# Bluetooth_Bridge_v16_Schematic_EasyEDA.net
KiCad netlist of a schematic drawn in EasyEDA
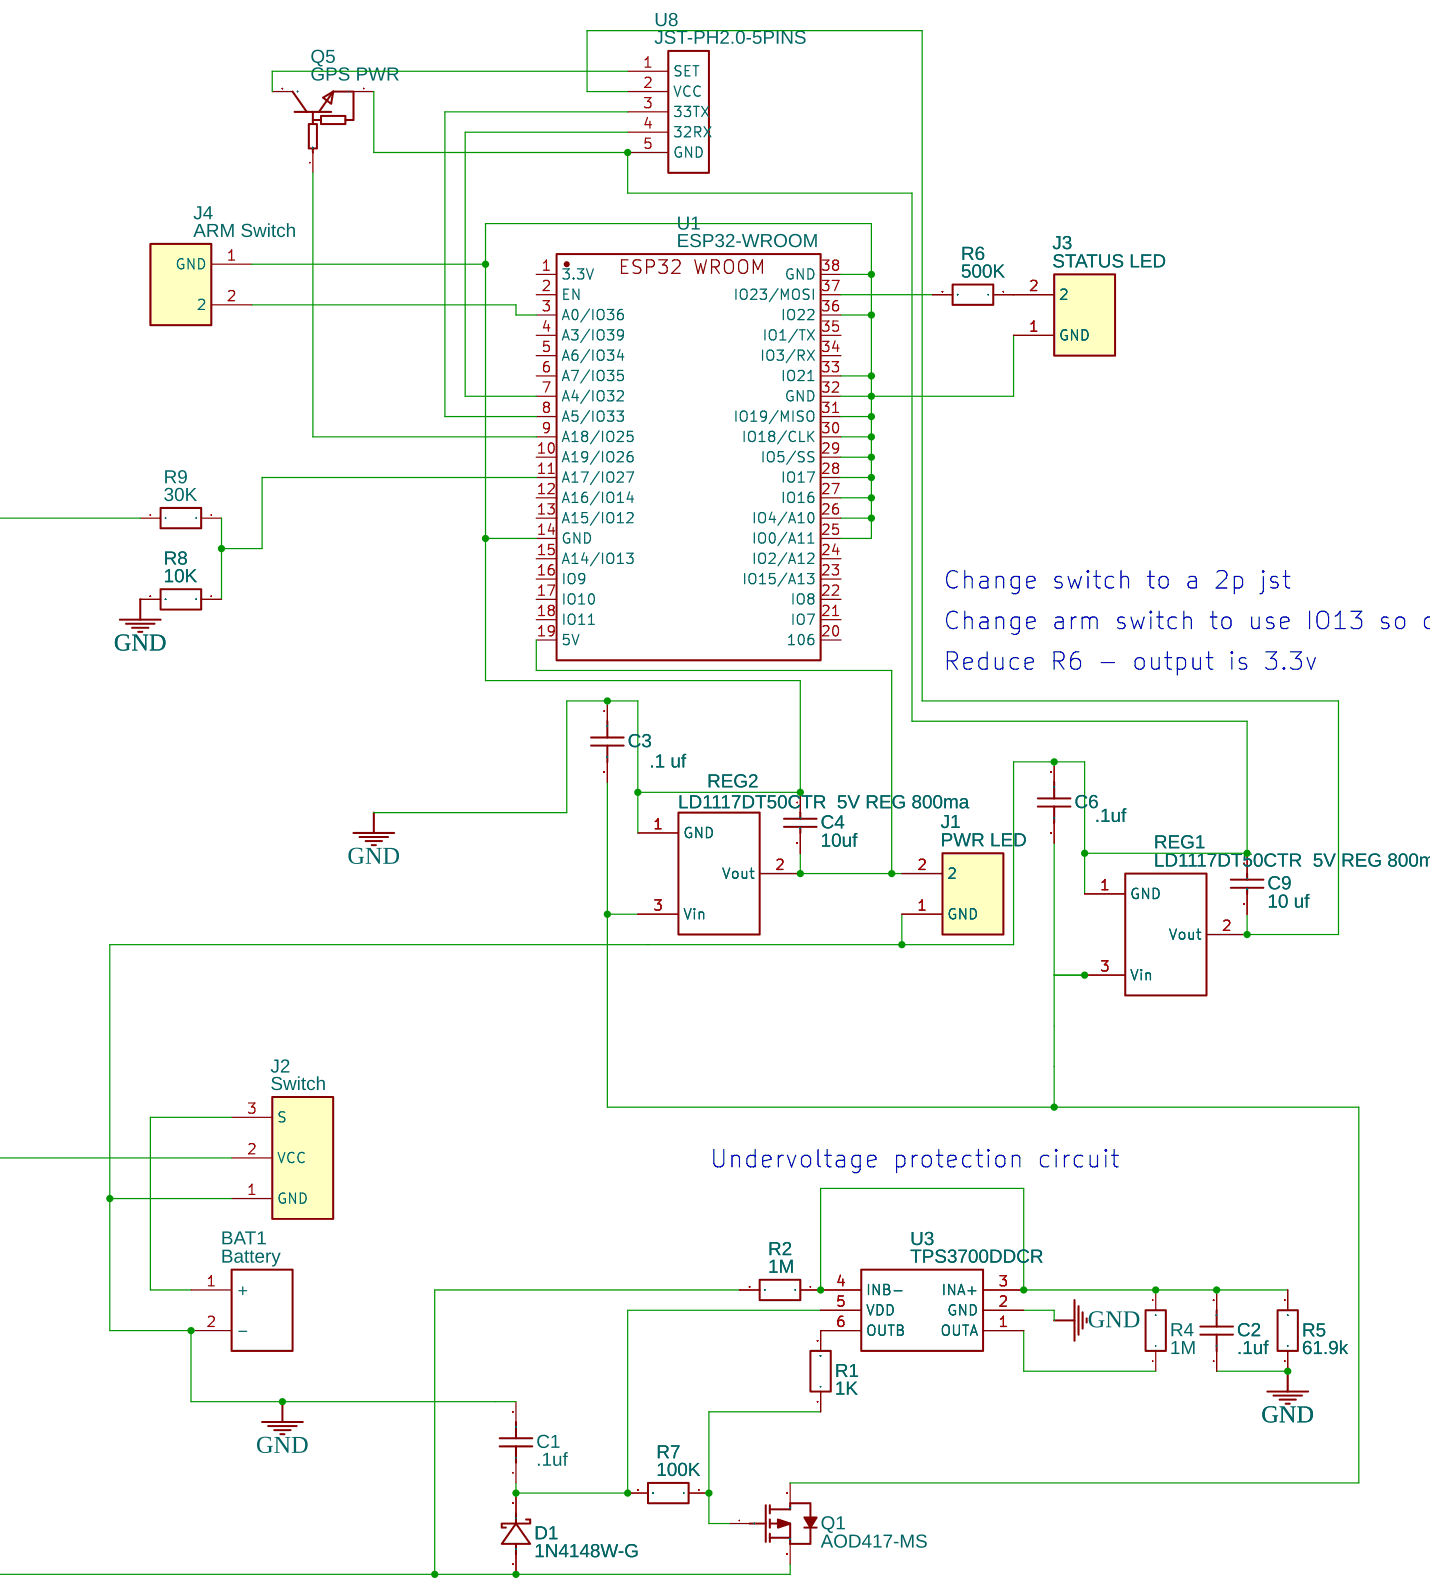
[diagram p0: schematic sheet]

(export (version "E")
  (design (tool "Eeschema 10.0.6"))
  (components
    (comp (ref "BAT1")
      (value "Battery")
      (fields
        (field (name "Manufacturer Part") "MKDSN1.5/2-5.08")
        (field (name "Manufacturer") "Phoenix Contact")
      )
      (libsource (lib "") (part "Unknown_85_-285"))
    )
    (comp (ref "C1")
      (value ".1uf")
      (fields
        (field (name "Manufacturer Part") "CS2012X7R105K500NRE")
        (field (name "Manufacturer") "Samwha Capacitor")
      )
      (libsource (lib "") (part "CS2012X7R105K500NRE"))
    )
    (comp (ref "C2")
      (value ".1uf")
      (fields
        (field (name "Manufacturer Part") "CS2012X7R105K500NRE")
        (field (name "Manufacturer") "Samwha Capacitor")
      )
      (libsource (lib "") (part "CS2012X7R105K500NRE"))
    )
    (comp (ref "C3")
      (value ".1 uf")
      (fields (field (name "Manufacturer Part") "CC0402KRX7R6BB104") (field (name "Manufacturer") "YAGEO"))
      (libsource (lib "") (part "CC0402KRX7R6BB104"))
    )
    (comp (ref "C4")
      (value "10uf")
      (fields (field (name "Manufacturer Part") "CL05A106MQ5NUNC") (field (name "Manufacturer") "SAMSUNG"))
      (libsource (lib "") (part "CL05A106MQ5NUNC"))
    )
    (comp (ref "C6")
      (value ".1uf")
      (fields (field (name "Manufacturer Part") "CC0402KRX7R6BB104") (field (name "Manufacturer") "YAGEO"))
      (libsource (lib "") (part "CC0402KRX7R6BB104"))
    )
    (comp (ref "C9")
      (value "10 uf")
      (fields (field (name "Manufacturer Part") "CL05A106MQ5NUNC") (field (name "Manufacturer") "SAMSUNG"))
      (libsource (lib "") (part "CL05A106MQ5NUNC"))
    )
    (comp (ref "D1")
      (value "1N4148W-G")
      (fields (field (name "Manufacturer Part") "DS16W(S16)-SOD123"))
      (libsource (lib "") (part "DS16W(S16)-SOD123"))
    )
    (comp (ref "J1")
      (value "PWR LED")
      (fields (field (name "Manufacturer Part") "B2B-PH-K-S(LF)(SN)") (field (name "Manufacturer") "JST"))
      (libsource (lib "") (part "B2B-PH-K-S(LF)(SN)"))
    )
    (comp (ref "J2")
      (value "Switch")
      (fields (field (name "Manufacturer Part") "B3B-PH-K-S(LF)(SN)") (field (name "Manufacturer") "JST"))
      (libsource (lib "") (part "Unknown_105_-360"))
    )
    (comp (ref "J3")
      (value "STATUS LED")
      (fields (field (name "Manufacturer Part") "B2B-PH-K-S(LF)(SN)") (field (name "Manufacturer") "JST"))
      (libsource (lib "") (part "B2B-PH-K-S(LF)(SN)"))
    )
    (comp (ref "J4")
      (value "ARM Switch")
      (fields (field (name "Manufacturer Part") "B2B-PH-K-S(LF)(SN)") (field (name "Manufacturer") "JST"))
      (libsource (lib "") (part "B2B-PH-K-S(LF)(SN)_1"))
    )
    (comp (ref "Q1")
      (value "AOD417-MS")
      (fields (field (name "Manufacturer") "MSKSEMI(美森科)"))
      (libsource (lib "") (part "AOD417-MS"))
    )
    (comp (ref "Q5")
      (value "GPS PWR")
      (fields (field (name "Manufacturer Part") "PDTC114EU,135") (field (name "Manufacturer") "Nexperia"))
      (libsource (lib "") (part "PDTC114EU,135"))
    )
    (comp (ref "R1")
      (value "1K")
      (fields (field (name "Manufacturer Part") "ERJP06J221V") (field (name "Manufacturer") "PANASONIC"))
      (libsource (lib "") (part "ERJP06J221V"))
    )
    (comp (ref "R2")
      (value "1M")
      (fields (field (name "Manufacturer Part") "ERJP06J221V") (field (name "Manufacturer") "PANASONIC"))
      (libsource (lib "") (part "ERJP06J221V_1"))
    )
    (comp (ref "R4")
      (value "1M")
      (fields (field (name "Manufacturer Part") "ERJP06J221V") (field (name "Manufacturer") "PANASONIC"))
      (libsource (lib "") (part "ERJP06J221V"))
    )
    (comp (ref "R5")
      (value "61.9k")
      (fields (field (name "Manufacturer Part") "ERJP06J221V") (field (name "Manufacturer") "PANASONIC"))
      (libsource (lib "") (part "ERJP06J221V"))
    )
    (comp (ref "R6")
      (value "500K")
      (fields (field (name "Manufacturer Part") "ERJP06J221V") (field (name "Manufacturer") "PANASONIC"))
      (libsource (lib "") (part "ERJP06J221V_1"))
    )
    (comp (ref "R7")
      (value "100K")
      (fields (field (name "Manufacturer Part") "ERJP06J221V") (field (name "Manufacturer") "PANASONIC"))
      (libsource (lib "") (part "ERJP06J221V_1"))
    )
    (comp (ref "R8")
      (value "10K")
      (fields (field (name "Manufacturer Part") "SFR03EZPF1001") (field (name "Manufacturer") "ROHM(罗姆)"))
      (libsource (lib "") (part "SFR03EZPF1001"))
    )
    (comp (ref "R9")
      (value "30K")
      (fields (field (name "Manufacturer Part") "SFR03EZPF1001") (field (name "Manufacturer") "ROHM(罗姆)"))
      (libsource (lib "") (part "SFR03EZPF1001"))
    )
    (comp (ref "REG1")
      (value "LD1117DT50CTR  5V REG 800ma")
      (fields (field (name "Manufacturer Part") "LD1117AG-12-TN3-A-R") (field (name "Manufacturer") "UTC"))
      (libsource (lib "") (part "LD1117AG-12-TN3-A-R"))
    )
    (comp (ref "REG2")
      (value "LD1117DT50CTR  5V REG 800ma")
      (fields (field (name "Manufacturer Part") "LD1117AG-12-TN3-A-R") (field (name "Manufacturer") "UTC"))
      (libsource (lib "") (part "LD1117AG-12-TN3-A-R"))
    )
    (comp (ref "U1")
      (value "ESP32-WROOM")
      (fields (field (name "Manufacturer Part") "3-01-1287") (field (name "Manufacturer") "HiLetgo"))
      (libsource (lib "") (part "Unknown_305_-705"))
    )
    (comp (ref "U3")
      (value "TPS3700DDCR")
      (fields (field (name "Manufacturer") "TI"))
      (libsource (lib "") (part "TPS3700DDCR"))
    )
    (comp (ref "U8") (value "JST-PH2.0-5PINS") (libsource (lib "") (part "JST-PH2.0-5PINS")))
  )
  (nets
    (net (code "1") (name "GND") (class "Default")
      (node (ref "BAT1") (pin "2") (pinfunction "-_2") (pintype "unspecified"))
      (node (ref "C1") (pin "2") (pinfunction "2_2") (pintype "unspecified"))
      (node (ref "C2") (pin "1") (pinfunction "1_1") (pintype "unspecified"))
      (node (ref "C3") (pin "1") (pinfunction "1_1") (pintype "unspecified"))
      (node (ref "C4") (pin "1") (pinfunction "1_1") (pintype "input"))
      (node (ref "C6") (pin "1") (pinfunction "1_1") (pintype "unspecified"))
      (node (ref "C9") (pin "1") (pinfunction "1_1") (pintype "input"))
      (node (ref "J1") (pin "1") (pinfunction "GND_1") (pintype "input"))
      (node (ref "J2") (pin "1") (pinfunction "GND_1") (pintype "input"))
      (node (ref "J3") (pin "1") (pinfunction "GND_1") (pintype "input"))
      (node (ref "J4") (pin "1") (pinfunction "GND_1") (pintype "input"))
      (node (ref "Q5") (pin "2") (pinfunction "E_2") (pintype "unspecified"))
      (node (ref "R5") (pin "1") (pinfunction "1_1") (pintype "unspecified"))
      (node (ref "R8") (pin "2") (pinfunction "2_2") (pintype "unspecified"))
      (node (ref "REG1") (pin "1") (pinfunction "GND_1") (pintype "unspecified"))
      (node (ref "REG2") (pin "1") (pinfunction "GND_1") (pintype "unspecified"))
      (node (ref "U1") (pin "14") (pinfunction "GND_14") (pintype "unspecified"))
      (node (ref "U1") (pin "25") (pinfunction "IO0/A11_25") (pintype "unspecified"))
      (node (ref "U1") (pin "26") (pinfunction "IO4/A10_26") (pintype "unspecified"))
      (node (ref "U1") (pin "27") (pinfunction "IO16_27") (pintype "unspecified"))
      (node (ref "U1") (pin "28") (pinfunction "IO17_28") (pintype "unspecified"))
      (node (ref "U1") (pin "29") (pinfunction "IO5/SS_29") (pintype "unspecified"))
      (node (ref "U1") (pin "30") (pinfunction "IO18/CLK_30") (pintype "unspecified"))
      (node (ref "U1") (pin "31") (pinfunction "IO19/MISO_31") (pintype "unspecified"))
      (node (ref "U1") (pin "32") (pinfunction "GND_32") (pintype "unspecified"))
      (node (ref "U1") (pin "33") (pinfunction "IO21_33") (pintype "unspecified"))
      (node (ref "U1") (pin "36") (pinfunction "IO22_36") (pintype "unspecified"))
      (node (ref "U1") (pin "38") (pinfunction "GND_38") (pintype "unspecified"))
      (node (ref "U3") (pin "2") (pinfunction "GND_2") (pintype "unspecified"))
      (node (ref "U8") (pin "5") (pinfunction "GND_5") (pintype "unspecified"))
    )
    (net (code "2") (name "Net-(BAT1-+)") (class "Default")
      (node (ref "BAT1") (pin "1") (pinfunction "+_1") (pintype "unspecified"))
      (node (ref "J2") (pin "3") (pinfunction "S_3") (pintype "input"))
    )
    (net (code "3") (name "Net-(D1-A)") (class "Default")
      (node (ref "D1") (pin "1") (pinfunction "A_1") (pintype "unspecified"))
      (node (ref "J2") (pin "2") (pinfunction "VCC_2") (pintype "input"))
      (node (ref "Q1") (pin "3") (pinfunction "S_3") (pintype "unspecified"))
      (node (ref "R2") (pin "2") (pinfunction "2_2") (pintype "unspecified"))
      (node (ref "R9") (pin "2") (pinfunction "2_2") (pintype "unspecified"))
    )
    (net (code "4") (name "Net-(D1-K)") (class "Default")
      (node (ref "C1") (pin "1") (pinfunction "1_1") (pintype "unspecified"))
      (node (ref "D1") (pin "2") (pinfunction "K_2") (pintype "unspecified"))
      (node (ref "R7") (pin "2") (pinfunction "2_2") (pintype "unspecified"))
      (node (ref "U3") (pin "5") (pinfunction "VDD_5") (pintype "unspecified"))
    )
    (net (code "5") (name "Net-(J3-Pad2)") (class "Default")
      (node (ref "J3") (pin "2") (pinfunction "2_2") (pintype "input"))
      (node (ref "R6") (pin "1") (pinfunction "1_1") (pintype "unspecified"))
    )
    (net (code "6") (name "Net-(Q1-D)") (class "Default")
      (node (ref "C3") (pin "2") (pinfunction "2_2") (pintype "unspecified"))
      (node (ref "C6") (pin "2") (pinfunction "2_2") (pintype "unspecified"))
      (node (ref "Q1") (pin "2") (pinfunction "D_2") (pintype "unspecified"))
      (node (ref "REG1") (pin "3") (pinfunction "Vin_3") (pintype "unspecified"))
      (node (ref "REG2") (pin "3") (pinfunction "Vin_3") (pintype "unspecified"))
    )
    (net (code "7") (name "Net-(Q1-G)") (class "Default")
      (node (ref "Q1") (pin "1") (pinfunction "G_1") (pintype "unspecified"))
      (node (ref "R1") (pin "1") (pinfunction "1_1") (pintype "unspecified"))
      (node (ref "R7") (pin "1") (pinfunction "1_1") (pintype "unspecified"))
    )
    (net (code "8") (name "Net-(Q5-B)") (class "Default")
      (node (ref "Q5") (pin "1") (pinfunction "B_1") (pintype "unspecified"))
      (node (ref "U1") (pin "9") (pinfunction "A18/IO25_9") (pintype "unspecified"))
    )
    (net (code "9") (name "Net-(Q5-C)") (class "Default")
      (node (ref "Q5") (pin "3") (pinfunction "C_3") (pintype "unspecified"))
      (node (ref "U8") (pin "1") (pinfunction "SET_1") (pintype "unspecified"))
    )
    (net (code "10") (name "Net-(REG1-Vout)") (class "Default")
      (node (ref "C9") (pin "2") (pinfunction "2_2") (pintype "input"))
      (node (ref "REG1") (pin "2") (pinfunction "Vout_2") (pintype "unspecified"))
      (node (ref "U8") (pin "2") (pinfunction "VCC_2") (pintype "unspecified"))
    )
    (net (code "11") (name "Net-(REG2-Vout)") (class "Default")
      (node (ref "C4") (pin "2") (pinfunction "2_2") (pintype "input"))
      (node (ref "J1") (pin "2") (pinfunction "2_2") (pintype "input"))
      (node (ref "REG2") (pin "2") (pinfunction "Vout_2") (pintype "unspecified"))
      (node (ref "U1") (pin "19") (pinfunction "5V_19") (pintype "unspecified"))
    )
    (net (code "12") (name "Net-(U1-A0{slash}IO36)") (class "Default")
      (node (ref "J4") (pin "2") (pinfunction "2_2") (pintype "input"))
      (node (ref "U1") (pin "3") (pinfunction "A0/IO36_3") (pintype "unspecified"))
    )
    (net (code "13") (name "Net-(U1-A4{slash}IO32)") (class "Default")
      (node (ref "U1") (pin "7") (pinfunction "A4/IO32_7") (pintype "unspecified"))
      (node (ref "U8") (pin "4") (pinfunction "32RX_4") (pintype "unspecified"))
    )
    (net (code "14") (name "Net-(U1-A5{slash}IO33)") (class "Default")
      (node (ref "U1") (pin "8") (pinfunction "A5/IO33_8") (pintype "unspecified"))
      (node (ref "U8") (pin "3") (pinfunction "33TX_3") (pintype "unspecified"))
    )
    (net (code "15") (name "Net-(U1-A17{slash}IO27)") (class "Default")
      (node (ref "R8") (pin "1") (pinfunction "1_1") (pintype "unspecified"))
      (node (ref "R9") (pin "1") (pinfunction "1_1") (pintype "unspecified"))
      (node (ref "U1") (pin "11") (pinfunction "A17/IO27_11") (pintype "unspecified"))
    )
    (net (code "16") (name "Net-(U1-IO23{slash}MOSI)") (class "Default")
      (node (ref "R6") (pin "2") (pinfunction "2_2") (pintype "unspecified"))
      (node (ref "U1") (pin "37") (pinfunction "IO23/MOSI_37") (pintype "unspecified"))
    )
    (net (code "17") (name "Net-(U3-INA+)") (class "Default")
      (node (ref "C2") (pin "2") (pinfunction "2_2") (pintype "unspecified"))
      (node (ref "R2") (pin "1") (pinfunction "1_1") (pintype "unspecified"))
      (node (ref "R4") (pin "2") (pinfunction "2_2") (pintype "unspecified"))
      (node (ref "R5") (pin "2") (pinfunction "2_2") (pintype "unspecified"))
      (node (ref "U3") (pin "3") (pinfunction "INA+_3") (pintype "unspecified"))
      (node (ref "U3") (pin "4") (pinfunction "INB-_4") (pintype "unspecified"))
    )
    (net (code "18") (name "Net-(U3-OUTA)") (class "Default")
      (node (ref "R4") (pin "1") (pinfunction "1_1") (pintype "unspecified"))
      (node (ref "U3") (pin "1") (pinfunction "OUTA_1") (pintype "unspecified"))
    )
    (net (code "19") (name "Net-(U3-OUTB)") (class "Default")
      (node (ref "R1") (pin "2") (pinfunction "2_2") (pintype "unspecified"))
      (node (ref "U3") (pin "6") (pinfunction "OUTB_6") (pintype "unspecified"))
    )
    (net (code "20") (name "unconnected-(U1-3.3V-Pad1)") (class "Default")
      (node (ref "U1") (pin "1") (pinfunction "3.3V_1") (pintype "unspecified"))
    )
    (net (code "21") (name "unconnected-(U1-106-Pad20)") (class "Default")
      (node (ref "U1") (pin "20") (pinfunction "106_20") (pintype "unspecified"))
    )
    (net (code "22") (name "unconnected-(U1-A3{slash}IO39-Pad4)") (class "Default")
      (node (ref "U1") (pin "4") (pinfunction "A3/IO39_4") (pintype "unspecified"))
    )
    (net (code "23") (name "unconnected-(U1-A6{slash}IO34-Pad5)") (class "Default")
      (node (ref "U1") (pin "5") (pinfunction "A6/IO34_5") (pintype "unspecified"))
    )
    (net (code "24") (name "unconnected-(U1-A7{slash}IO35-Pad6)") (class "Default")
      (node (ref "U1") (pin "6") (pinfunction "A7/IO35_6") (pintype "unspecified"))
    )
    (net (code "25") (name "unconnected-(U1-A14{slash}IO13-Pad15)") (class "Default")
      (node (ref "U1") (pin "15") (pinfunction "A14/IO13_15") (pintype "unspecified"))
    )
    (net (code "26") (name "unconnected-(U1-A15{slash}IO12-Pad13)") (class "Default")
      (node (ref "U1") (pin "13") (pinfunction "A15/IO12_13") (pintype "unspecified"))
    )
    (net (code "27") (name "unconnected-(U1-A16{slash}IO14-Pad12)") (class "Default")
      (node (ref "U1") (pin "12") (pinfunction "A16/IO14_12") (pintype "unspecified"))
    )
    (net (code "28") (name "unconnected-(U1-A19{slash}IO26-Pad10)") (class "Default")
      (node (ref "U1") (pin "10") (pinfunction "A19/IO26_10") (pintype "unspecified"))
    )
    (net (code "29") (name "unconnected-(U1-EN-Pad2)") (class "Default")
      (node (ref "U1") (pin "2") (pinfunction "EN_2") (pintype "unspecified"))
    )
    (net (code "30") (name "unconnected-(U1-IO1{slash}TX-Pad35)") (class "Default")
      (node (ref "U1") (pin "35") (pinfunction "IO1/TX_35") (pintype "unspecified"))
    )
    (net (code "31") (name "unconnected-(U1-IO2{slash}A12-Pad24)") (class "Default")
      (node (ref "U1") (pin "24") (pinfunction "IO2/A12_24") (pintype "unspecified"))
    )
    (net (code "32") (name "unconnected-(U1-IO3{slash}RX-Pad34)") (class "Default")
      (node (ref "U1") (pin "34") (pinfunction "IO3/RX_34") (pintype "unspecified"))
    )
    (net (code "33") (name "unconnected-(U1-IO7-Pad21)") (class "Default")
      (node (ref "U1") (pin "21") (pinfunction "IO7_21") (pintype "unspecified"))
    )
    (net (code "34") (name "unconnected-(U1-IO8-Pad22)") (class "Default")
      (node (ref "U1") (pin "22") (pinfunction "IO8_22") (pintype "unspecified"))
    )
    (net (code "35") (name "unconnected-(U1-IO9-Pad16)") (class "Default")
      (node (ref "U1") (pin "16") (pinfunction "IO9_16") (pintype "unspecified"))
    )
    (net (code "36") (name "unconnected-(U1-IO10-Pad17)") (class "Default")
      (node (ref "U1") (pin "17") (pinfunction "IO10_17") (pintype "unspecified"))
    )
    (net (code "37") (name "unconnected-(U1-IO11-Pad18)") (class "Default")
      (node (ref "U1") (pin "18") (pinfunction "IO11_18") (pintype "unspecified"))
    )
    (net (code "38") (name "unconnected-(U1-IO15{slash}A13-Pad23)") (class "Default")
      (node (ref "U1") (pin "23") (pinfunction "IO15/A13_23") (pintype "unspecified"))
    )
  )
)
